# SCH_Shuffl_2024-09-28.net
KiCad netlist of a schematic drawn in EasyEDA
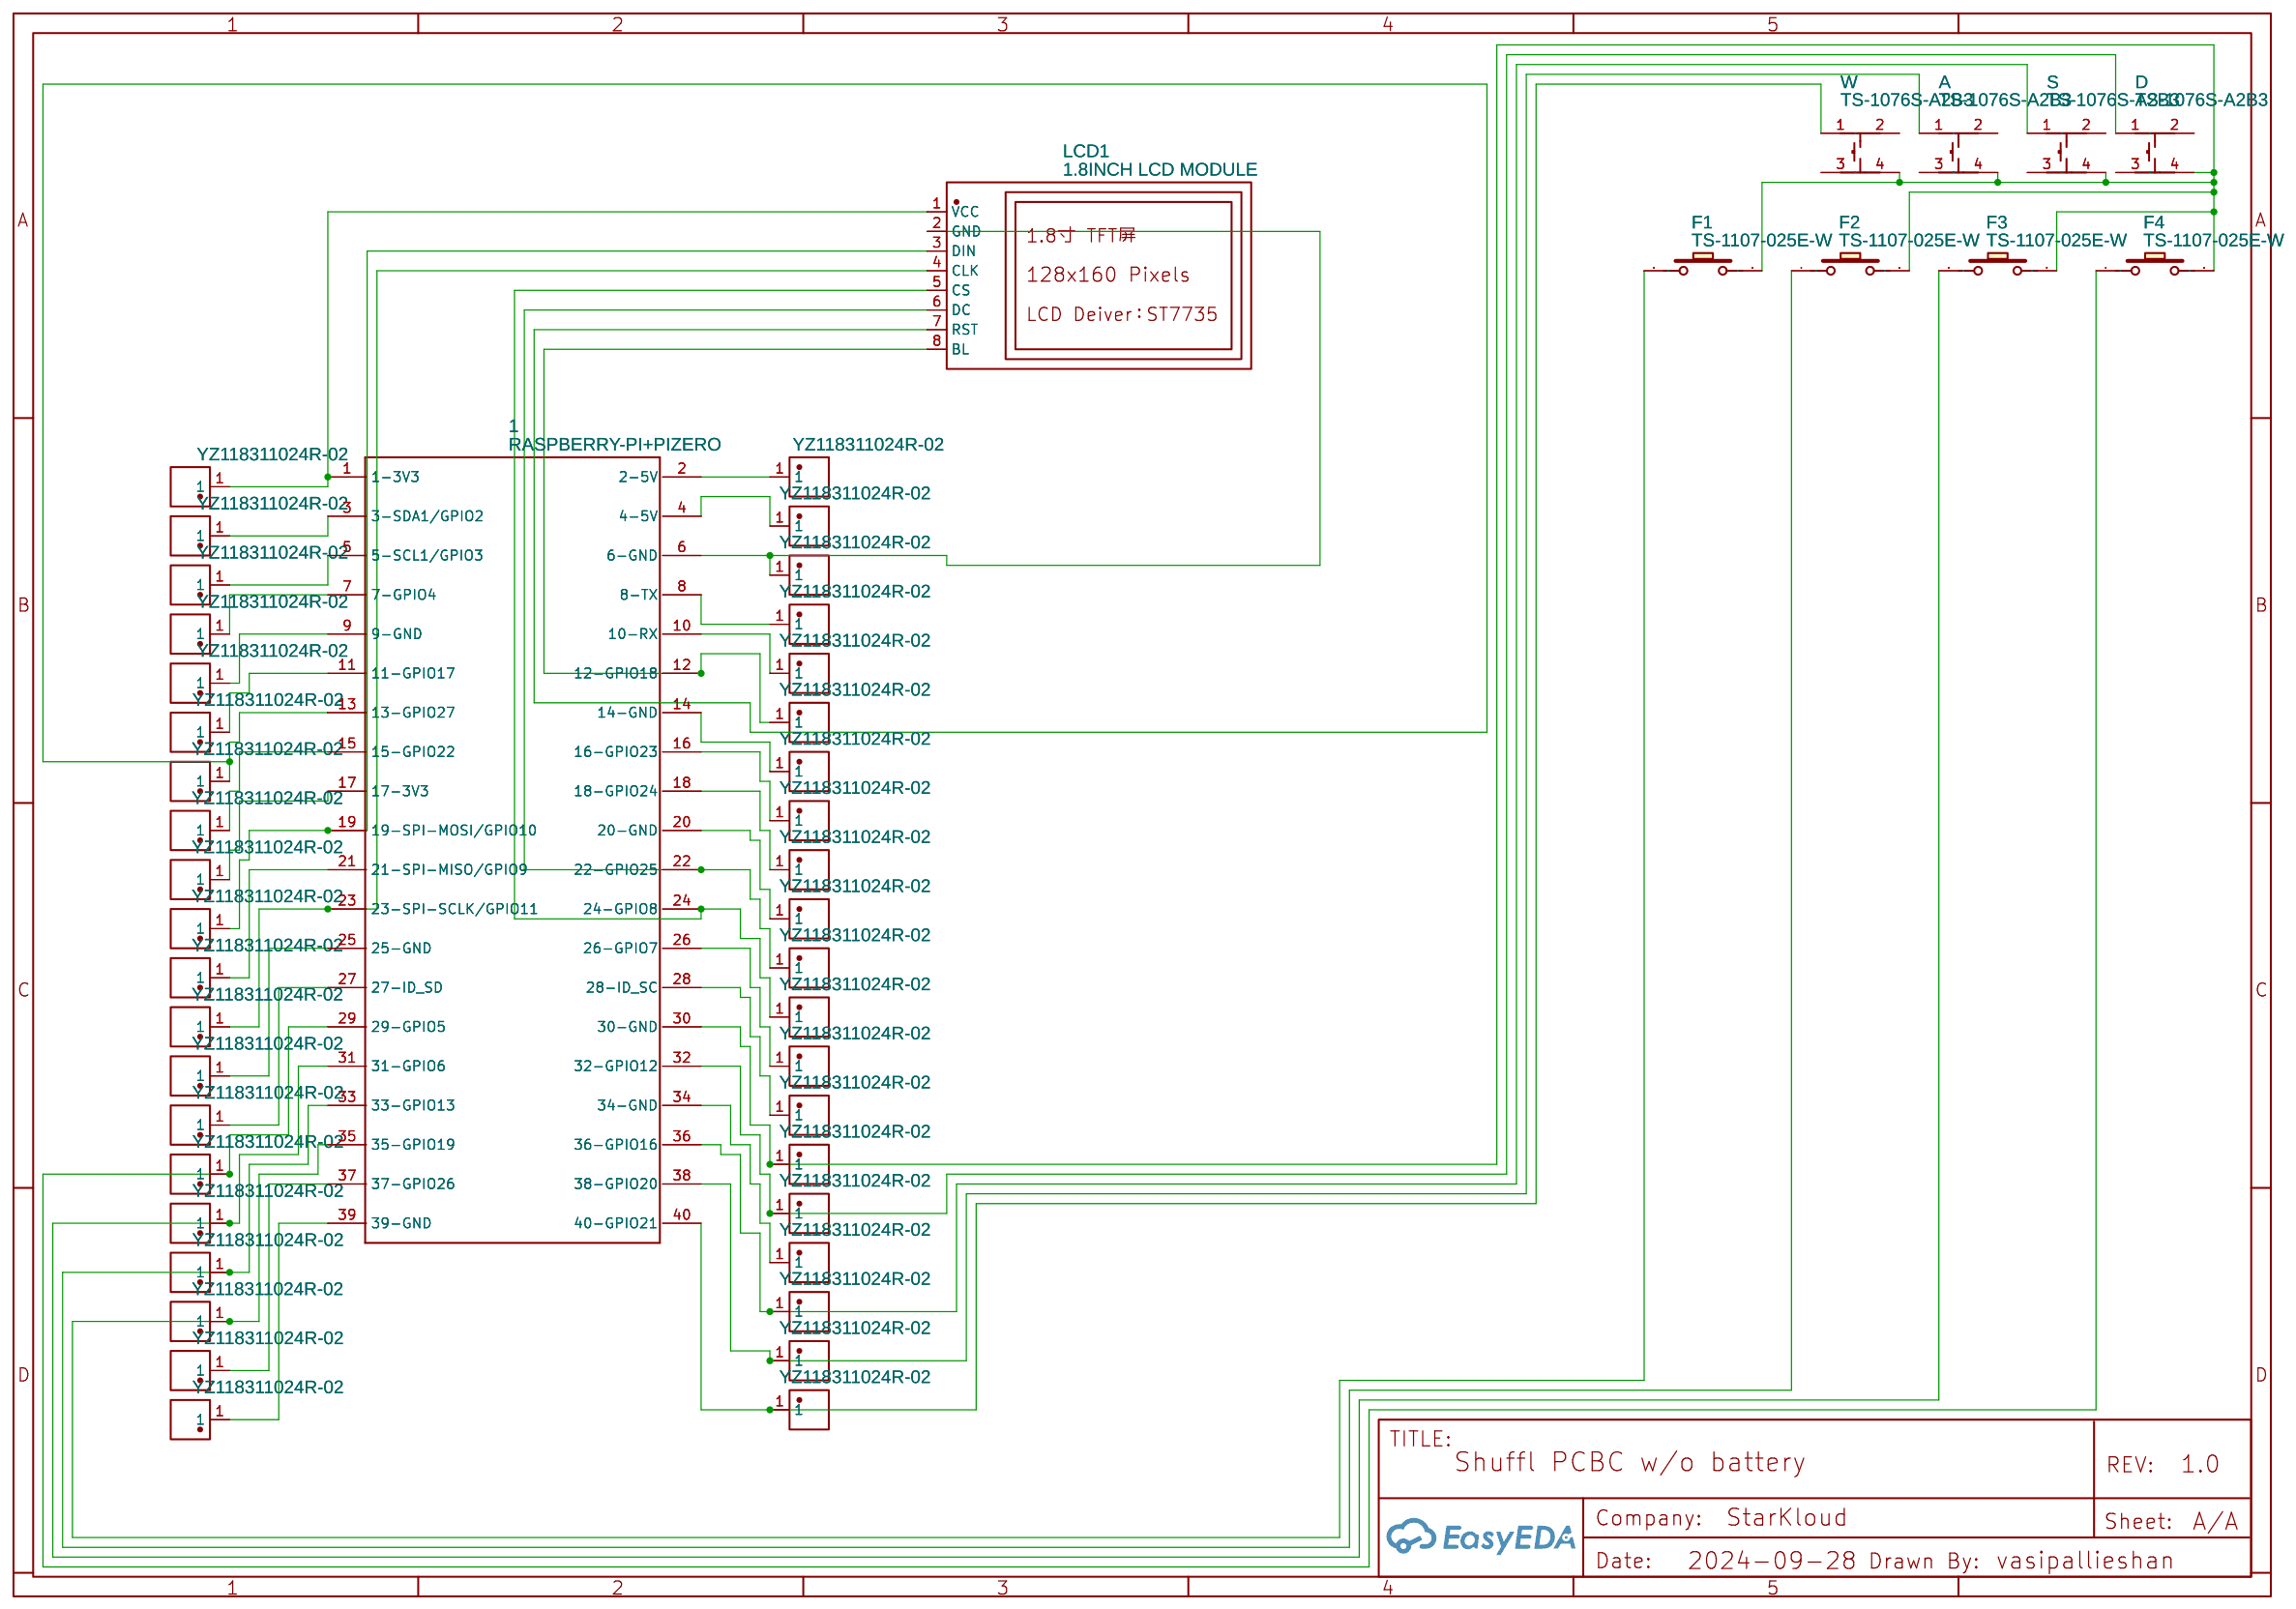
[diagram p0: schematic sheet]

(export (version "E")
  (design (tool "Eeschema 10.0.6"))
  (components
    (comp (ref "1") (value "RASPBERRY-PI+PIZERO") (libsource (lib "") (part "RASPBERRY-PI+PIZERO")))
    (comp (ref "2")
      (value "YZ118311024R-02")
      (fields (field (name "Manufacturer") "Xinyangze(鑫扬泽)"))
      (libsource (lib "") (part "YZ118311024R-02_1"))
    )
    (comp (ref "3")
      (value "YZ118311024R-02")
      (fields (field (name "Manufacturer") "Xinyangze(鑫扬泽)"))
      (libsource (lib "") (part "YZ118311024R-02"))
    )
    (comp (ref "4")
      (value "YZ118311024R-02")
      (fields (field (name "Manufacturer") "Xinyangze(鑫扬泽)"))
      (libsource (lib "") (part "YZ118311024R-02_1"))
    )
    (comp (ref "5")
      (value "YZ118311024R-02")
      (fields (field (name "Manufacturer") "Xinyangze(鑫扬泽)"))
      (libsource (lib "") (part "YZ118311024R-02"))
    )
    (comp (ref "6")
      (value "YZ118311024R-02")
      (fields (field (name "Manufacturer") "Xinyangze(鑫扬泽)"))
      (libsource (lib "") (part "YZ118311024R-02_1"))
    )
    (comp (ref "7")
      (value "YZ118311024R-02")
      (fields (field (name "Manufacturer") "Xinyangze(鑫扬泽)"))
      (libsource (lib "") (part "YZ118311024R-02"))
    )
    (comp (ref "8")
      (value "YZ118311024R-02")
      (fields (field (name "Manufacturer") "Xinyangze(鑫扬泽)"))
      (libsource (lib "") (part "YZ118311024R-02_1"))
    )
    (comp (ref "9")
      (value "YZ118311024R-02")
      (fields (field (name "Manufacturer") "Xinyangze(鑫扬泽)"))
      (libsource (lib "") (part "YZ118311024R-02"))
    )
    (comp (ref "10")
      (value "YZ118311024R-02")
      (fields (field (name "Manufacturer") "Xinyangze(鑫扬泽)"))
      (libsource (lib "") (part "YZ118311024R-02_1"))
    )
    (comp (ref "11")
      (value "YZ118311024R-02")
      (fields (field (name "Manufacturer") "Xinyangze(鑫扬泽)"))
      (libsource (lib "") (part "YZ118311024R-02"))
    )
    (comp (ref "12")
      (value "YZ118311024R-02")
      (fields (field (name "Manufacturer") "Xinyangze(鑫扬泽)"))
      (libsource (lib "") (part "YZ118311024R-02_1"))
    )
    (comp (ref "13")
      (value "YZ118311024R-02")
      (fields (field (name "Manufacturer") "Xinyangze(鑫扬泽)"))
      (libsource (lib "") (part "YZ118311024R-02"))
    )
    (comp (ref "14")
      (value "YZ118311024R-02")
      (fields (field (name "Manufacturer") "Xinyangze(鑫扬泽)"))
      (libsource (lib "") (part "YZ118311024R-02_1"))
    )
    (comp (ref "15")
      (value "YZ118311024R-02")
      (fields (field (name "Manufacturer") "Xinyangze(鑫扬泽)"))
      (libsource (lib "") (part "YZ118311024R-02"))
    )
    (comp (ref "16")
      (value "YZ118311024R-02")
      (fields (field (name "Manufacturer") "Xinyangze(鑫扬泽)"))
      (libsource (lib "") (part "YZ118311024R-02_1"))
    )
    (comp (ref "17")
      (value "YZ118311024R-02")
      (fields (field (name "Manufacturer") "Xinyangze(鑫扬泽)"))
      (libsource (lib "") (part "YZ118311024R-02"))
    )
    (comp (ref "18")
      (value "YZ118311024R-02")
      (fields (field (name "Manufacturer") "Xinyangze(鑫扬泽)"))
      (libsource (lib "") (part "YZ118311024R-02_1"))
    )
    (comp (ref "19")
      (value "YZ118311024R-02")
      (fields (field (name "Manufacturer") "Xinyangze(鑫扬泽)"))
      (libsource (lib "") (part "YZ118311024R-02"))
    )
    (comp (ref "20")
      (value "YZ118311024R-02")
      (fields (field (name "Manufacturer") "Xinyangze(鑫扬泽)"))
      (libsource (lib "") (part "YZ118311024R-02_1"))
    )
    (comp (ref "21")
      (value "YZ118311024R-02")
      (fields (field (name "Manufacturer") "Xinyangze(鑫扬泽)"))
      (libsource (lib "") (part "YZ118311024R-02"))
    )
    (comp (ref "22")
      (value "YZ118311024R-02")
      (fields (field (name "Manufacturer") "Xinyangze(鑫扬泽)"))
      (libsource (lib "") (part "YZ118311024R-02_1"))
    )
    (comp (ref "23")
      (value "YZ118311024R-02")
      (fields (field (name "Manufacturer") "Xinyangze(鑫扬泽)"))
      (libsource (lib "") (part "YZ118311024R-02"))
    )
    (comp (ref "24")
      (value "YZ118311024R-02")
      (fields (field (name "Manufacturer") "Xinyangze(鑫扬泽)"))
      (libsource (lib "") (part "YZ118311024R-02_1"))
    )
    (comp (ref "25")
      (value "YZ118311024R-02")
      (fields (field (name "Manufacturer") "Xinyangze(鑫扬泽)"))
      (libsource (lib "") (part "YZ118311024R-02"))
    )
    (comp (ref "26")
      (value "YZ118311024R-02")
      (fields (field (name "Manufacturer") "Xinyangze(鑫扬泽)"))
      (libsource (lib "") (part "YZ118311024R-02_1"))
    )
    (comp (ref "27")
      (value "YZ118311024R-02")
      (fields (field (name "Manufacturer") "Xinyangze(鑫扬泽)"))
      (libsource (lib "") (part "YZ118311024R-02"))
    )
    (comp (ref "28")
      (value "YZ118311024R-02")
      (fields (field (name "Manufacturer") "Xinyangze(鑫扬泽)"))
      (libsource (lib "") (part "YZ118311024R-02_1"))
    )
    (comp (ref "29")
      (value "YZ118311024R-02")
      (fields (field (name "Manufacturer") "Xinyangze(鑫扬泽)"))
      (libsource (lib "") (part "YZ118311024R-02"))
    )
    (comp (ref "30")
      (value "YZ118311024R-02")
      (fields (field (name "Manufacturer") "Xinyangze(鑫扬泽)"))
      (libsource (lib "") (part "YZ118311024R-02_1"))
    )
    (comp (ref "31")
      (value "YZ118311024R-02")
      (fields (field (name "Manufacturer") "Xinyangze(鑫扬泽)"))
      (libsource (lib "") (part "YZ118311024R-02"))
    )
    (comp (ref "32")
      (value "YZ118311024R-02")
      (fields (field (name "Manufacturer") "Xinyangze(鑫扬泽)"))
      (libsource (lib "") (part "YZ118311024R-02_1"))
    )
    (comp (ref "33")
      (value "YZ118311024R-02")
      (fields (field (name "Manufacturer") "Xinyangze(鑫扬泽)"))
      (libsource (lib "") (part "YZ118311024R-02"))
    )
    (comp (ref "34")
      (value "YZ118311024R-02")
      (fields (field (name "Manufacturer") "Xinyangze(鑫扬泽)"))
      (libsource (lib "") (part "YZ118311024R-02_1"))
    )
    (comp (ref "35")
      (value "YZ118311024R-02")
      (fields (field (name "Manufacturer") "Xinyangze(鑫扬泽)"))
      (libsource (lib "") (part "YZ118311024R-02"))
    )
    (comp (ref "36")
      (value "YZ118311024R-02")
      (fields (field (name "Manufacturer") "Xinyangze(鑫扬泽)"))
      (libsource (lib "") (part "YZ118311024R-02_1"))
    )
    (comp (ref "37")
      (value "YZ118311024R-02")
      (fields (field (name "Manufacturer") "Xinyangze(鑫扬泽)"))
      (libsource (lib "") (part "YZ118311024R-02"))
    )
    (comp (ref "38")
      (value "YZ118311024R-02")
      (fields (field (name "Manufacturer") "Xinyangze(鑫扬泽)"))
      (libsource (lib "") (part "YZ118311024R-02_1"))
    )
    (comp (ref "39")
      (value "YZ118311024R-02")
      (fields (field (name "Manufacturer") "Xinyangze(鑫扬泽)"))
      (libsource (lib "") (part "YZ118311024R-02"))
    )
    (comp (ref "40")
      (value "YZ118311024R-02")
      (fields (field (name "Manufacturer") "Xinyangze(鑫扬泽)"))
      (libsource (lib "") (part "YZ118311024R-02_1"))
    )
    (comp (ref "A")
      (value "TS-1076S-A2B3")
      (fields (field (name "Manufacturer Part") "?"))
      (libsource (lib "") (part "Unknown_0_-806"))
    )
    (comp (ref "D")
      (value "TS-1076S-A2B3")
      (fields (field (name "Manufacturer") "Yuandi(元迪)"))
      (libsource (lib "") (part "TS-1076S-A2B3_2"))
    )
    (comp (ref "F1")
      (value "TS-1107-025E-W")
      (fields (field (name "Manufacturer") "HOOYA(皓宇电子)"))
      (libsource (lib "") (part "TS-1107-025E-W"))
    )
    (comp (ref "F2")
      (value "TS-1107-025E-W")
      (fields (field (name "Manufacturer") "HOOYA(皓宇电子)"))
      (libsource (lib "") (part "TS-1107-025E-W"))
    )
    (comp (ref "F3")
      (value "TS-1107-025E-W")
      (fields (field (name "Manufacturer") "HOOYA(皓宇电子)"))
      (libsource (lib "") (part "TS-1107-025E-W"))
    )
    (comp (ref "F4")
      (value "TS-1107-025E-W")
      (fields (field (name "Manufacturer") "HOOYA(皓宇电子)"))
      (libsource (lib "") (part "TS-1107-025E-W"))
    )
    (comp (ref "GP")
      (value "YZ118311024R-02")
      (fields (field (name "Manufacturer") "Xinyangze(鑫扬泽)"))
      (libsource (lib "") (part "YZ118311024R-02_2"))
    )
    (comp (ref "LCD1")
      (value "1.8INCH LCD MODULE")
      (fields
        (field (name "Manufacturer Part") "1.8inch LCD Module")
        (field (name "Manufacturer") "Waveshare(微雪电子)")
      )
      (libsource (lib "") (part "1.8INCH LCD MODULE"))
    )
    (comp (ref "S")
      (value "TS-1076S-A2B3")
      (fields (field (name "Manufacturer") "Yuandi(元迪)"))
      (libsource (lib "") (part "TS-1076S-A2B3_1"))
    )
    (comp (ref "W")
      (value "TS-1076S-A2B3")
      (fields (field (name "Manufacturer") "Yuandi(元迪)"))
      (libsource (lib "") (part "TS-1076S-A2B3_3"))
    )
  )
  (nets
    (net (code "1") (name "Net-(1-1-3V3)") (class "Default")
      (node (ref "1") (pin "1") (pinfunction "1-3V3_1") (pintype "bidirectional"))
      (node (ref "GP") (pin "1") (pinfunction "1_1") (pintype "unspecified"))
      (node (ref "LCD1") (pin "1") (pinfunction "VCC_1") (pintype "unspecified"))
    )
    (net (code "2") (name "Net-(1-2-5V)") (class "Default")
      (node (ref "1") (pin "2") (pinfunction "2-5V_2") (pintype "bidirectional"))
      (node (ref "2") (pin "1") (pinfunction "1_1") (pintype "unspecified"))
    )
    (net (code "3") (name "Net-(1-3-SDA1{slash}GPIO2)") (class "Default")
      (node (ref "1") (pin "3") (pinfunction "3-SDA1/GPIO2_3") (pintype "bidirectional"))
      (node (ref "3") (pin "1") (pinfunction "1_1") (pintype "unspecified"))
    )
    (net (code "4") (name "Net-(1-4-5V)") (class "Default")
      (node (ref "1") (pin "4") (pinfunction "4-5V_4") (pintype "bidirectional"))
      (node (ref "4") (pin "1") (pinfunction "1_1") (pintype "unspecified"))
    )
    (net (code "5") (name "Net-(1-5-SCL1{slash}GPIO3)") (class "Default")
      (node (ref "1") (pin "5") (pinfunction "5-SCL1/GPIO3_5") (pintype "bidirectional"))
      (node (ref "5") (pin "1") (pinfunction "1_1") (pintype "unspecified"))
    )
    (net (code "6") (name "Net-(1-6-GND)") (class "Default")
      (node (ref "1") (pin "6") (pinfunction "6-GND_6") (pintype "bidirectional"))
      (node (ref "6") (pin "1") (pinfunction "1_1") (pintype "unspecified"))
      (node (ref "LCD1") (pin "2") (pinfunction "GND_2") (pintype "unspecified"))
    )
    (net (code "7") (name "Net-(1-7-GPIO4)") (class "Default")
      (node (ref "1") (pin "7") (pinfunction "7-GPIO4_7") (pintype "bidirectional"))
      (node (ref "7") (pin "1") (pinfunction "1_1") (pintype "unspecified"))
    )
    (net (code "8") (name "Net-(1-8-TX)") (class "Default")
      (node (ref "1") (pin "8") (pinfunction "8-TX_8") (pintype "bidirectional"))
      (node (ref "8") (pin "1") (pinfunction "1_1") (pintype "unspecified"))
    )
    (net (code "9") (name "Net-(1-9-GND)") (class "Default")
      (node (ref "1") (pin "9") (pinfunction "9-GND_9") (pintype "bidirectional"))
      (node (ref "9") (pin "1") (pinfunction "1_1") (pintype "unspecified"))
    )
    (net (code "10") (name "Net-(1-10-RX)") (class "Default")
      (node (ref "1") (pin "10") (pinfunction "10-RX_10") (pintype "bidirectional"))
      (node (ref "10") (pin "1") (pinfunction "1_1") (pintype "unspecified"))
    )
    (net (code "11") (name "Net-(1-11-GPIO17)") (class "Default")
      (node (ref "1") (pin "11") (pinfunction "11-GPIO17_11") (pintype "bidirectional"))
      (node (ref "11") (pin "1") (pinfunction "1_1") (pintype "unspecified"))
    )
    (net (code "12") (name "Net-(1-12-GPIO18)") (class "Default")
      (node (ref "1") (pin "12") (pinfunction "12-GPIO18_12") (pintype "bidirectional"))
      (node (ref "12") (pin "1") (pinfunction "1_1") (pintype "unspecified"))
      (node (ref "LCD1") (pin "8") (pinfunction "BL_8") (pintype "unspecified"))
    )
    (net (code "13") (name "Net-(1-13-GPIO27)") (class "Default")
      (node (ref "1") (pin "13") (pinfunction "13-GPIO27_13") (pintype "bidirectional"))
      (node (ref "13") (pin "1") (pinfunction "1_1") (pintype "unspecified"))
      (node (ref "LCD1") (pin "7") (pinfunction "RST_7") (pintype "unspecified"))
    )
    (net (code "14") (name "Net-(1-14-GND)") (class "Default")
      (node (ref "1") (pin "14") (pinfunction "14-GND_14") (pintype "bidirectional"))
      (node (ref "14") (pin "1") (pinfunction "1_1") (pintype "unspecified"))
    )
    (net (code "15") (name "Net-(1-15-GPIO22)") (class "Default")
      (node (ref "1") (pin "15") (pinfunction "15-GPIO22_15") (pintype "bidirectional"))
      (node (ref "15") (pin "1") (pinfunction "1_1") (pintype "unspecified"))
    )
    (net (code "16") (name "Net-(1-16-GPIO23)") (class "Default")
      (node (ref "1") (pin "16") (pinfunction "16-GPIO23_16") (pintype "bidirectional"))
      (node (ref "16") (pin "1") (pinfunction "1_1") (pintype "unspecified"))
    )
    (net (code "17") (name "Net-(1-17-3V3)") (class "Default")
      (node (ref "1") (pin "17") (pinfunction "17-3V3_17") (pintype "bidirectional"))
      (node (ref "17") (pin "1") (pinfunction "1_1") (pintype "unspecified"))
    )
    (net (code "18") (name "Net-(1-18-GPIO24)") (class "Default")
      (node (ref "1") (pin "18") (pinfunction "18-GPIO24_18") (pintype "bidirectional"))
      (node (ref "18") (pin "1") (pinfunction "1_1") (pintype "unspecified"))
    )
    (net (code "19") (name "Net-(1-19-SPI-MOSI{slash}GPIO10)") (class "Default")
      (node (ref "1") (pin "19") (pinfunction "19-SPI-MOSI/GPIO10_19") (pintype "bidirectional"))
      (node (ref "19") (pin "1") (pinfunction "1_1") (pintype "unspecified"))
      (node (ref "LCD1") (pin "3") (pinfunction "DIN_3") (pintype "unspecified"))
    )
    (net (code "20") (name "Net-(1-20-GND)") (class "Default")
      (node (ref "1") (pin "20") (pinfunction "20-GND_20") (pintype "bidirectional"))
      (node (ref "20") (pin "1") (pinfunction "1_1") (pintype "unspecified"))
    )
    (net (code "21") (name "Net-(1-21-SPI-MISO{slash}GPIO9)") (class "Default")
      (node (ref "1") (pin "21") (pinfunction "21-SPI-MISO/GPIO9_21") (pintype "bidirectional"))
      (node (ref "21") (pin "1") (pinfunction "1_1") (pintype "unspecified"))
    )
    (net (code "22") (name "Net-(1-22-GPIO25)") (class "Default")
      (node (ref "1") (pin "22") (pinfunction "22-GPIO25_22") (pintype "bidirectional"))
      (node (ref "22") (pin "1") (pinfunction "1_1") (pintype "unspecified"))
      (node (ref "LCD1") (pin "6") (pinfunction "DC_6") (pintype "unspecified"))
    )
    (net (code "23") (name "Net-(1-23-SPI-SCLK{slash}GPIO11)") (class "Default")
      (node (ref "1") (pin "23") (pinfunction "23-SPI-SCLK/GPIO11_23") (pintype "bidirectional"))
      (node (ref "23") (pin "1") (pinfunction "1_1") (pintype "unspecified"))
      (node (ref "LCD1") (pin "4") (pinfunction "CLK_4") (pintype "unspecified"))
    )
    (net (code "24") (name "Net-(1-24-GPIO8)") (class "Default")
      (node (ref "1") (pin "24") (pinfunction "24-GPIO8_24") (pintype "bidirectional"))
      (node (ref "24") (pin "1") (pinfunction "1_1") (pintype "unspecified"))
      (node (ref "LCD1") (pin "5") (pinfunction "CS_5") (pintype "unspecified"))
    )
    (net (code "25") (name "Net-(1-25-GND)") (class "Default")
      (node (ref "1") (pin "25") (pinfunction "25-GND_25") (pintype "bidirectional"))
      (node (ref "25") (pin "1") (pinfunction "1_1") (pintype "unspecified"))
    )
    (net (code "26") (name "Net-(1-26-GPIO7)") (class "Default")
      (node (ref "1") (pin "26") (pinfunction "26-GPIO7_26") (pintype "bidirectional"))
      (node (ref "26") (pin "1") (pinfunction "1_1") (pintype "unspecified"))
    )
    (net (code "27") (name "Net-(1-27-ID_SD)") (class "Default")
      (node (ref "1") (pin "27") (pinfunction "27-ID_SD_27") (pintype "bidirectional"))
      (node (ref "27") (pin "1") (pinfunction "1_1") (pintype "unspecified"))
    )
    (net (code "28") (name "Net-(1-28-ID_SC)") (class "Default")
      (node (ref "1") (pin "28") (pinfunction "28-ID_SC_28") (pintype "bidirectional"))
      (node (ref "28") (pin "1") (pinfunction "1_1") (pintype "unspecified"))
    )
    (net (code "29") (name "Net-(1-29-GPIO5)") (class "Default")
      (node (ref "1") (pin "29") (pinfunction "29-GPIO5_29") (pintype "bidirectional"))
      (node (ref "29") (pin "1") (pinfunction "1_1") (pintype "unspecified"))
      (node (ref "F4") (pin "1") (pinfunction "1_1") (pintype "unspecified"))
    )
    (net (code "30") (name "Net-(1-30-GND)") (class "Default")
      (node (ref "1") (pin "30") (pinfunction "30-GND_30") (pintype "bidirectional"))
      (node (ref "30") (pin "1") (pinfunction "1_1") (pintype "unspecified"))
      (node (ref "A") (pin "4") (pinfunction "4_4") (pintype "unspecified"))
      (node (ref "D") (pin "4") (pinfunction "4_4") (pintype "unspecified"))
      (node (ref "F1") (pin "2") (pinfunction "2_2") (pintype "unspecified"))
      (node (ref "F2") (pin "2") (pinfunction "2_2") (pintype "unspecified"))
      (node (ref "F3") (pin "2") (pinfunction "2_2") (pintype "unspecified"))
      (node (ref "F4") (pin "2") (pinfunction "2_2") (pintype "unspecified"))
      (node (ref "S") (pin "4") (pinfunction "4_4") (pintype "unspecified"))
      (node (ref "W") (pin "4") (pinfunction "4_4") (pintype "unspecified"))
    )
    (net (code "31") (name "Net-(1-31-GPIO6)") (class "Default")
      (node (ref "1") (pin "31") (pinfunction "31-GPIO6_31") (pintype "bidirectional"))
      (node (ref "31") (pin "1") (pinfunction "1_1") (pintype "unspecified"))
      (node (ref "F3") (pin "1") (pinfunction "1_1") (pintype "unspecified"))
    )
    (net (code "32") (name "Net-(1-32-GPIO12)") (class "Default")
      (node (ref "1") (pin "32") (pinfunction "32-GPIO12_32") (pintype "bidirectional"))
      (node (ref "32") (pin "1") (pinfunction "1_1") (pintype "unspecified"))
      (node (ref "D") (pin "1") (pinfunction "1_1") (pintype "unspecified"))
    )
    (net (code "33") (name "Net-(1-33-GPIO13)") (class "Default")
      (node (ref "1") (pin "33") (pinfunction "33-GPIO13_33") (pintype "bidirectional"))
      (node (ref "33") (pin "1") (pinfunction "1_1") (pintype "unspecified"))
      (node (ref "F2") (pin "1") (pinfunction "1_1") (pintype "unspecified"))
    )
    (net (code "34") (name "Net-(1-34-GND)") (class "Default")
      (node (ref "1") (pin "34") (pinfunction "34-GND_34") (pintype "bidirectional"))
      (node (ref "34") (pin "1") (pinfunction "1_1") (pintype "unspecified"))
    )
    (net (code "35") (name "Net-(1-35-GPIO19)") (class "Default")
      (node (ref "1") (pin "35") (pinfunction "35-GPIO19_35") (pintype "bidirectional"))
      (node (ref "35") (pin "1") (pinfunction "1_1") (pintype "unspecified"))
      (node (ref "F1") (pin "1") (pinfunction "1_1") (pintype "unspecified"))
    )
    (net (code "36") (name "Net-(1-36-GPIO16)") (class "Default")
      (node (ref "1") (pin "36") (pinfunction "36-GPIO16_36") (pintype "bidirectional"))
      (node (ref "36") (pin "1") (pinfunction "1_1") (pintype "unspecified"))
      (node (ref "S") (pin "1") (pinfunction "1_1") (pintype "unspecified"))
    )
    (net (code "37") (name "Net-(1-37-GPIO26)") (class "Default")
      (node (ref "1") (pin "37") (pinfunction "37-GPIO26_37") (pintype "bidirectional"))
      (node (ref "37") (pin "1") (pinfunction "1_1") (pintype "unspecified"))
    )
    (net (code "38") (name "Net-(1-38-GPIO20)") (class "Default")
      (node (ref "1") (pin "38") (pinfunction "38-GPIO20_38") (pintype "bidirectional"))
      (node (ref "38") (pin "1") (pinfunction "1_1") (pintype "unspecified"))
      (node (ref "A") (pin "1") (pinfunction "1_1") (pintype "unspecified"))
    )
    (net (code "39") (name "Net-(1-39-GND)") (class "Default")
      (node (ref "1") (pin "39") (pinfunction "39-GND_39") (pintype "bidirectional"))
      (node (ref "39") (pin "1") (pinfunction "1_1") (pintype "unspecified"))
    )
    (net (code "40") (name "Net-(1-40-GPIO21)") (class "Default")
      (node (ref "1") (pin "40") (pinfunction "40-GPIO21_40") (pintype "bidirectional"))
      (node (ref "40") (pin "1") (pinfunction "1_1") (pintype "unspecified"))
      (node (ref "W") (pin "1") (pinfunction "1_1") (pintype "unspecified"))
    )
    (net (code "41") (name "unconnected-(A-Pad2)") (class "Default")
      (node (ref "A") (pin "2") (pinfunction "2_2") (pintype "unspecified"))
    )
    (net (code "42") (name "unconnected-(A-Pad3)") (class "Default")
      (node (ref "A") (pin "3") (pinfunction "3_3") (pintype "unspecified"))
    )
    (net (code "43") (name "unconnected-(D-Pad2)") (class "Default")
      (node (ref "D") (pin "2") (pinfunction "2_2") (pintype "unspecified"))
    )
    (net (code "44") (name "unconnected-(D-Pad3)") (class "Default")
      (node (ref "D") (pin "3") (pinfunction "3_3") (pintype "unspecified"))
    )
    (net (code "45") (name "unconnected-(S-Pad2)") (class "Default")
      (node (ref "S") (pin "2") (pinfunction "2_2") (pintype "unspecified"))
    )
    (net (code "46") (name "unconnected-(S-Pad3)") (class "Default")
      (node (ref "S") (pin "3") (pinfunction "3_3") (pintype "unspecified"))
    )
    (net (code "47") (name "unconnected-(W-Pad2)") (class "Default")
      (node (ref "W") (pin "2") (pinfunction "2_2") (pintype "unspecified"))
    )
    (net (code "48") (name "unconnected-(W-Pad3)") (class "Default")
      (node (ref "W") (pin "3") (pinfunction "3_3") (pintype "unspecified"))
    )
  )
)
